# Schematic_Day2.net
KiCad netlist of a schematic drawn in EAGLE
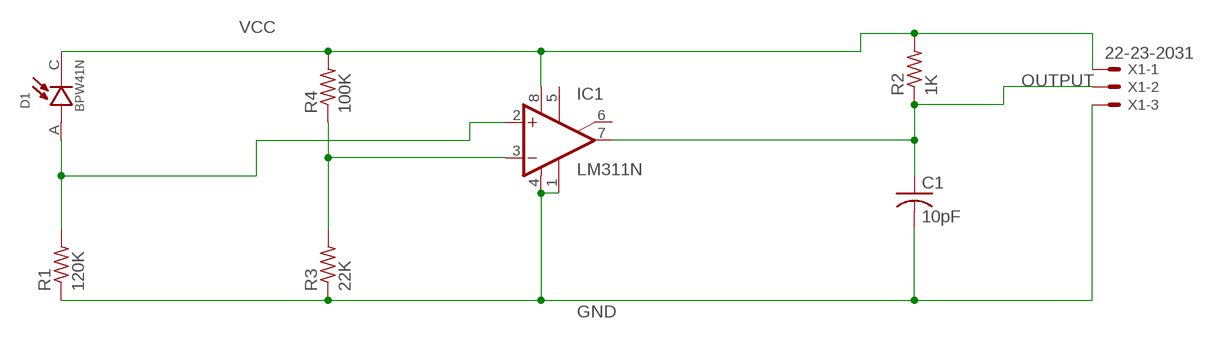
[diagram p0: schematic, sheet 1]

(export (version "E")
  (design (tool "Eeschema 10.0.6"))
  (components
    (comp (ref "C1")
      (value "10pF")
      (footprint "eagle-import:C025-024X044")
      (libsource (lib "eagle-import") (part "C-US025-024X044"))
    )
    (comp (ref "D1")
      (value "BPW41N")
      (footprint "eagle-import:DIO_BPW41N")
      (fields (field (name "MF") "Vishay Semiconductor Opto Division"))
      (libsource (lib "eagle-import") (part "BPW41N"))
    )
    (comp (ref "IC1")
      (value "LM311N")
      (footprint "eagle-import:DIL08")
      (libsource (lib "eagle-import") (part "LM311N"))
    )
    (comp (ref "R1")
      (value "120K")
      (footprint "eagle-import:0204_5")
      (libsource (lib "eagle-import") (part "R-US_0204/5"))
    )
    (comp (ref "R2")
      (value "1K")
      (footprint "eagle-import:0204_5")
      (libsource (lib "eagle-import") (part "R-US_0204/5"))
    )
    (comp (ref "R3")
      (value "22K")
      (footprint "eagle-import:0204_5")
      (libsource (lib "eagle-import") (part "R-US_0204/5"))
    )
    (comp (ref "R4")
      (value "100K")
      (footprint "eagle-import:0204_5")
      (libsource (lib "eagle-import") (part "R-US_0204/5"))
    )
    (comp (ref "X1")
      (value "22-23-2031")
      (footprint "eagle-import:22-23-2031")
      (fields (field (name "MF") "MOLEX"))
      (libsource (lib "eagle-import") (part "22-23-2031"))
    )
  )
  (nets
    (net (code "1") (name "/GND") (class "Default")
      (node (ref "C1") (pin "2") (pinfunction "2_2") (pintype "passive"))
      (node (ref "IC1") (pin "1") (pinfunction "GND_1") (pintype "passive"))
      (node (ref "IC1") (pin "4") (pinfunction "V-_4") (pintype "power_in"))
      (node (ref "R1") (pin "1") (pinfunction "1_1") (pintype "passive"))
      (node (ref "R3") (pin "1") (pinfunction "1_1") (pintype "passive"))
      (node (ref "X1") (pin "3") (pinfunction "S_3") (pintype "passive"))
    )
    (net (code "2") (name "/OUTPUT") (class "Default")
      (node (ref "C1") (pin "1") (pinfunction "1_1") (pintype "passive"))
      (node (ref "IC1") (pin "7") (pinfunction "OUT_7") (pintype "output"))
      (node (ref "R2") (pin "1") (pinfunction "1_1") (pintype "passive"))
      (node (ref "X1") (pin "2") (pinfunction "S_2") (pintype "passive"))
    )
    (net (code "3") (name "/VCC") (class "Default")
      (node (ref "D1") (pin "C") (pinfunction "C_C") (pintype "passive"))
      (node (ref "IC1") (pin "8") (pinfunction "V+_8") (pintype "power_in"))
      (node (ref "R2") (pin "2") (pinfunction "2_2") (pintype "passive"))
      (node (ref "R4") (pin "2") (pinfunction "2_2") (pintype "passive"))
      (node (ref "X1") (pin "1") (pinfunction "S_1") (pintype "passive"))
    )
    (net (code "4") (name "Net-(IC1-+IN)") (class "Default")
      (node (ref "D1") (pin "A") (pinfunction "A_A") (pintype "passive"))
      (node (ref "IC1") (pin "2") (pinfunction "+IN_2") (pintype "input"))
      (node (ref "R1") (pin "2") (pinfunction "2_2") (pintype "passive"))
    )
    (net (code "5") (name "Net-(IC1--IN)") (class "Default")
      (node (ref "IC1") (pin "3") (pinfunction "-IN_3") (pintype "input"))
      (node (ref "R3") (pin "2") (pinfunction "2_2") (pintype "passive"))
      (node (ref "R4") (pin "1") (pinfunction "1_1") (pintype "passive"))
    )
    (net (code "6") (name "unconnected-(IC1-ON-Pad5)") (class "Default")
      (node (ref "IC1") (pin "5") (pinfunction "ON_5") (pintype "passive"))
    )
    (net (code "7") (name "unconnected-(IC1-ON{slash}STR-Pad6)") (class "Default")
      (node (ref "IC1") (pin "6") (pinfunction "ON/STR_6") (pintype "passive"))
    )
  )
)
